# Option_PMIC_RK808.net
KiCad netlist of a schematic drawn in Altium Designer
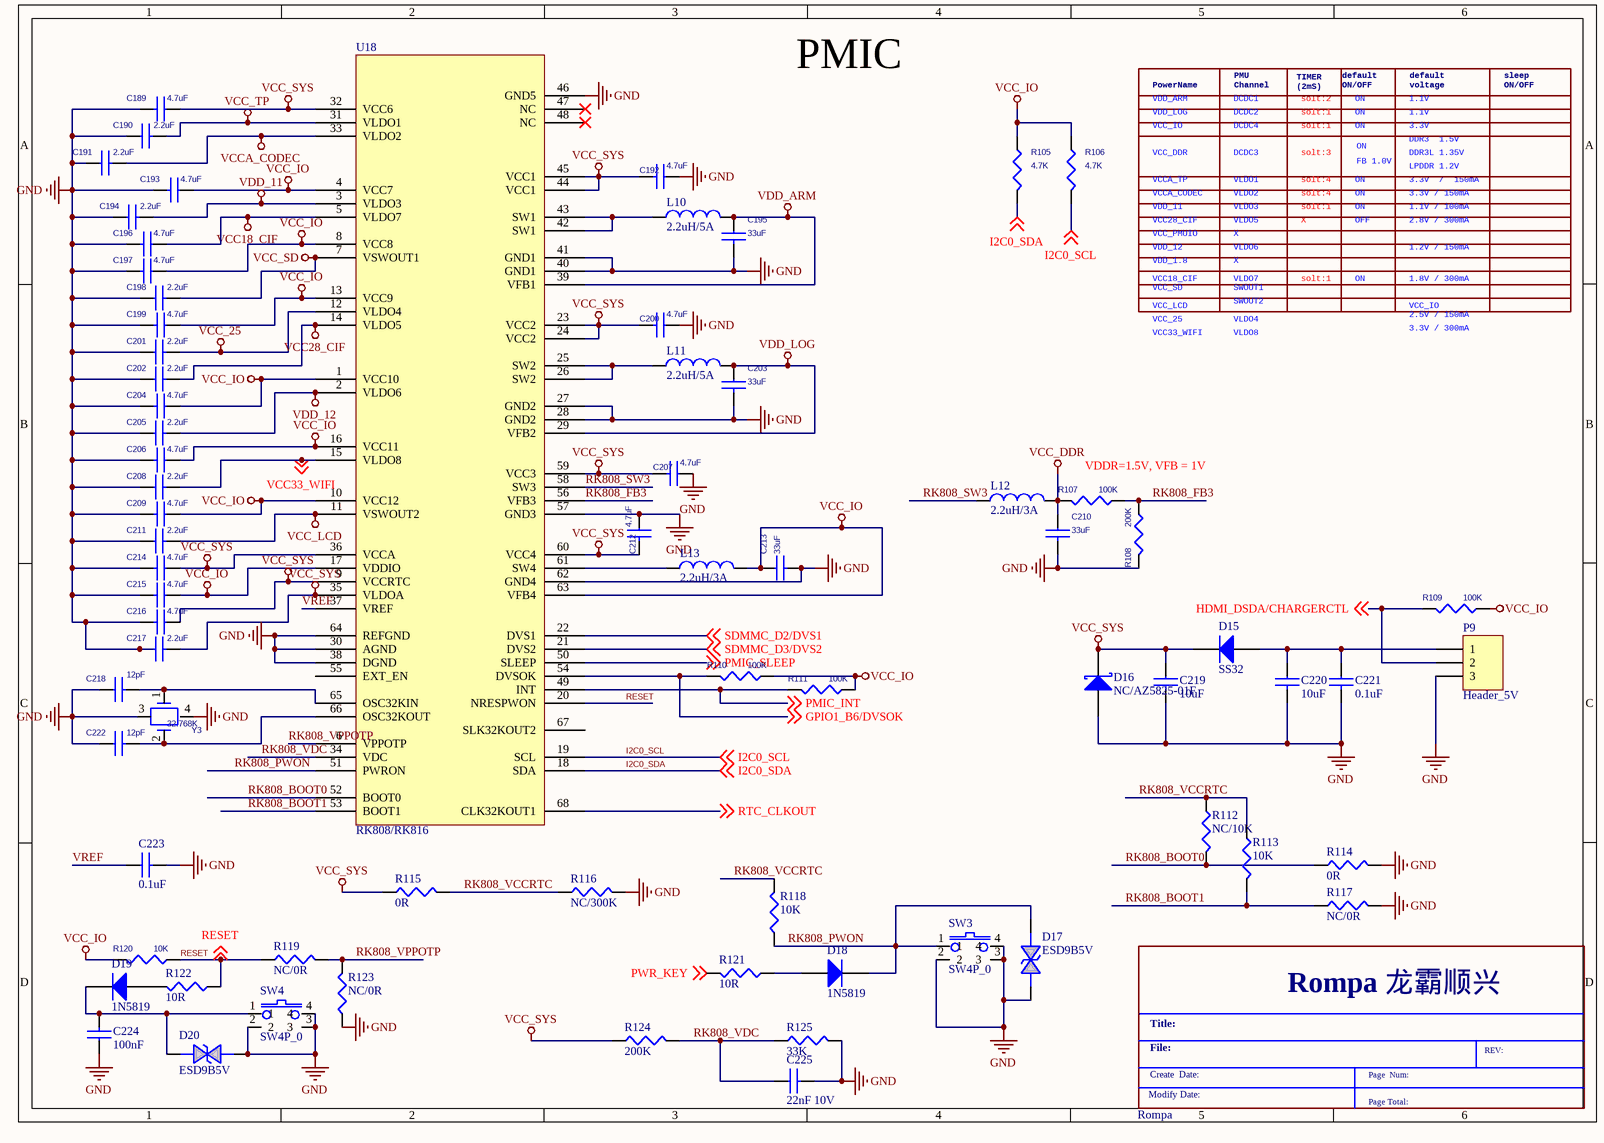
[diagram p0: Option_PMIC_RK808.SchDoc]

(export (version "E")
  (design (tool "Eeschema 10.0.6"))
  (components
    (comp (ref "C189") (value "4.7uF") (footprint "C0603") (libsource (lib "*") (part "CAP NP_4")))
    (comp (ref "C190") (value "2.2uF") (footprint "C0402") (libsource (lib "*") (part "CAP NP_4")))
    (comp (ref "C191") (value "2.2uF") (footprint "C0402") (libsource (lib "*") (part "CAP NP_4")))
    (comp (ref "C192") (value "4.7uF") (footprint "C0603") (libsource (lib "*") (part "CAP NP_4")))
    (comp (ref "C193") (value "4.7uF") (footprint "C0603") (libsource (lib "*") (part "CAP NP_4")))
    (comp (ref "C194") (value "2.2uF") (footprint "C0402") (libsource (lib "*") (part "CAP NP_4")))
    (comp (ref "C195") (value "33uF") (footprint "C0805") (libsource (lib "*") (part "CAP NP_4")))
    (comp (ref "C196") (value "4.7uF") (footprint "C0603") (libsource (lib "*") (part "CAP NP_4")))
    (comp (ref "C197") (value "4.7uF") (footprint "C0603") (libsource (lib "*") (part "CAP NP_4")))
    (comp (ref "C198") (value "2.2uF") (footprint "C0402") (libsource (lib "*") (part "CAP NP_4")))
    (comp (ref "C199") (value "4.7uF") (footprint "C0603") (libsource (lib "*") (part "CAP NP_4")))
    (comp (ref "C200") (value "4.7uF") (footprint "C0603") (libsource (lib "*") (part "CAP NP_4")))
    (comp (ref "C201") (value "2.2uF") (footprint "C0402") (libsource (lib "*") (part "CAP NP_4")))
    (comp (ref "C202") (value "2.2uF") (footprint "C0402") (libsource (lib "*") (part "CAP NP_4")))
    (comp (ref "C203") (value "33uF") (footprint "C0805") (libsource (lib "*") (part "CAP NP_4")))
    (comp (ref "C204") (value "4.7uF") (footprint "C0603") (libsource (lib "*") (part "CAP NP_4")))
    (comp (ref "C205") (value "2.2uF") (footprint "C0402") (libsource (lib "*") (part "CAP NP_4")))
    (comp (ref "C206") (value "4.7uF") (footprint "C0603") (libsource (lib "*") (part "CAP NP_4")))
    (comp (ref "C207") (value "4.7uF") (footprint "C0603") (libsource (lib "*") (part "CAP NP_4")))
    (comp (ref "C208") (value "2.2uF") (footprint "C0402") (libsource (lib "*") (part "CAP NP_4")))
    (comp (ref "C209") (value "4.7uF") (footprint "C0603") (libsource (lib "*") (part "CAP NP_4")))
    (comp (ref "C210") (value "33uF") (footprint "C0805") (libsource (lib "*") (part "CAP NP_4")))
    (comp (ref "C211") (value "2.2uF") (footprint "C0402") (libsource (lib "*") (part "CAP NP_4")))
    (comp (ref "C212") (value "4.7uF") (footprint "C0603") (libsource (lib "*") (part "CAP NP_4")))
    (comp (ref "C213") (value "33uF") (footprint "C0805") (libsource (lib "*") (part "CAP NP_4")))
    (comp (ref "C214") (value "4.7uF") (footprint "C0603") (libsource (lib "*") (part "CAP NP_4")))
    (comp (ref "C215") (value "4.7uF") (footprint "C0603") (libsource (lib "*") (part "CAP NP_4")))
    (comp (ref "C216") (value "4.7uF") (footprint "C0603") (libsource (lib "*") (part "CAP NP_4")))
    (comp (ref "C217") (value "2.2uF") (footprint "C0402") (libsource (lib "*") (part "CAP NP_4")))
    (comp (ref "C218") (value "12pF") (footprint "C0402") (libsource (lib "*") (part "CAP NP_4")))
    (comp (ref "C219")
      (value "10uF")
      (footprint "C0805")
      (description "10V X5R")
      (libsource (lib "RK3128_BETA_V03_20151231_Library") (part "CAP NP_Dup1"))
    )
    (comp (ref "C220")
      (value "10uF")
      (footprint "C0805")
      (description "10V X5R")
      (libsource (lib "RK3128_BETA_V03_20151231_Library") (part "CAP NP_Dup1"))
    )
    (comp (ref "C221")
      (value "0.1uF")
      (footprint "C0402")
      (libsource (lib "RK3128_BETA_V03_20151231_Library") (part "CAP NP"))
    )
    (comp (ref "C222") (value "12pF") (footprint "C0402") (libsource (lib "*") (part "CAP NP_4")))
    (comp (ref "C223")
      (value "0.1uF")
      (footprint "C0402")
      (libsource (lib "RK3128_BETA_V03_20151231_Library") (part "CAP NP"))
    )
    (comp (ref "C224")
      (value "100nF")
      (footprint "C0402")
      (description "16V X7R")
      (libsource (lib "RK3128_BETA_V03_20151231_Library") (part "CAP NP"))
    )
    (comp (ref "C225")
      (value "22nF 10V")
      (footprint "C0402")
      (libsource (lib "RK3128_BETA_V03_20151231_Library") (part "CAP NP"))
    )
    (comp (ref "D15")
      (value "SS32")
      (description "SOD123")
      (fields (field (name "PUBLISHER") "Altium Limited"))
      (libsource (lib "Miscellaneous Devices") (part "Diode"))
    )
    (comp (ref "D16")
      (value "NC/AZ5825-01F")
      (description "AMAZING, FP:DFN1006P2E")
      (fields (field (name "PUBLISHER") "Altium Limited"))
      (libsource (lib "Miscellaneous Devices") (part "Diode BAS70"))
    )
    (comp (ref "D17")
      (value "ESD9B5V")
      (description "FP:E0402N")
      (libsource (lib "RK3128_BETA_V03_20151231_Library") (part "DIODE BI-DIR TRIG"))
    )
    (comp (ref "D18")
      (value "1N5819")
      (fields (field (name "PUBLISHER") "Altium Limited"))
      (libsource (lib "Miscellaneous Devices") (part "Diode"))
    )
    (comp (ref "D19")
      (value "1N5819")
      (fields (field (name "PUBLISHER") "Altium Limited"))
      (libsource (lib "Miscellaneous Devices") (part "Diode"))
    )
    (comp (ref "D20")
      (value "ESD9B5V")
      (description "FP:E0402N")
      (libsource (lib "RK3128_BETA_V03_20151231_Library") (part "DIODE BI-DIR TRIG"))
    )
    (comp (ref "L10") (value "2.2uH/5A") (libsource (lib "Miscellaneous Devices") (part "Inductor")))
    (comp (ref "L11") (value "2.2uH/5A") (libsource (lib "Miscellaneous Devices") (part "Inductor")))
    (comp (ref "L12") (value "2.2uH/3A") (libsource (lib "Miscellaneous Devices") (part "Inductor")))
    (comp (ref "L13") (value "2.2uH/3A") (libsource (lib "Miscellaneous Devices") (part "Inductor")))
    (comp (ref "P9")
      (value "Header_5V")
      (footprint "HDR1X3")
      (description "Header, 3-Pin")
      (fields (field (name "PUBLISHER") "Altium Limited"))
      (libsource (lib "Miscellaneous Connectors") (part "Header 3"))
    )
    (comp (ref "R105")
      (value "4.7K")
      (footprint "R0402")
      (description "ROHS CHIP RES 4.7K 1/16W 5%")
      (libsource (lib "*") (part "RES 1B"))
    )
    (comp (ref "R106")
      (value "4.7K")
      (footprint "R0402")
      (description "ROHS CHIP RES 4.7K 1/16W 5%")
      (libsource (lib "*") (part "RES 1B"))
    )
    (comp (ref "R107")
      (value "100K")
      (footprint "R0402")
      (description "%1")
      (libsource (lib "*") (part "RESISTOR_1"))
    )
    (comp (ref "R108")
      (value "200K")
      (footprint "R0402")
      (description "%1")
      (libsource (lib "") (part "RESISTOR_1_1"))
    )
    (comp (ref "R109")
      (value "100K")
      (footprint "R0402")
      (description "RES,thick film,47KOhm,+/-5%,1/16W,SMD0402")
      (libsource (lib "*") (part "RESISTOR_1"))
    )
    (comp (ref "R110")
      (value "100K")
      (footprint "R0402")
      (description "RES,thick film,47KOhm,+/-5%,1/16W,SMD0402")
      (libsource (lib "*") (part "RESISTOR_1"))
    )
    (comp (ref "R111")
      (value "100K")
      (footprint "R0402")
      (description "RES,thick film,47KOhm,+/-5%,1/16W,SMD0402")
      (libsource (lib "*") (part "RESISTOR_1"))
    )
    (comp (ref "R112")
      (value "NC/10K")
      (footprint "R0402")
      (libsource (lib "RK3128_BETA_V03_20151231_Library") (part "RESISTOR"))
    )
    (comp (ref "R113")
      (value "10K")
      (footprint "R0402")
      (libsource (lib "RK3128_BETA_V03_20151231_Library") (part "RESISTOR"))
    )
    (comp (ref "R114")
      (value "0R")
      (footprint "R0402")
      (libsource (lib "RK3128_BETA_V03_20151231_Library") (part "RESISTOR"))
    )
    (comp (ref "R115")
      (value "0R")
      (footprint "R0402")
      (libsource (lib "RK3128_BETA_V03_20151231_Library") (part "RESISTOR"))
    )
    (comp (ref "R116")
      (value "NC/300K")
      (footprint "R0402")
      (libsource (lib "RK3128_BETA_V03_20151231_Library") (part "RESISTOR"))
    )
    (comp (ref "R117")
      (value "NC/0R")
      (footprint "R0402")
      (libsource (lib "RK3128_BETA_V03_20151231_Library") (part "RESISTOR"))
    )
    (comp (ref "R118")
      (value "10K")
      (footprint "R0402")
      (libsource (lib "RK3128_BETA_V03_20151231_Library") (part "RESISTOR"))
    )
    (comp (ref "R119")
      (value "NC/0R")
      (footprint "R0402")
      (libsource (lib "RK3128_BETA_V03_20151231_Library") (part "RESISTOR"))
    )
    (comp (ref "R120")
      (value "10K")
      (footprint "R0402")
      (description "RES,thick film,47KOhm,+/-5%,1/16W,SMD0402")
      (libsource (lib "*") (part "RESISTOR_1"))
    )
    (comp (ref "R121")
      (value "10R")
      (footprint "R0402")
      (libsource (lib "RK3128_BETA_V03_20151231_Library") (part "RESISTOR"))
    )
    (comp (ref "R122")
      (value "10R")
      (footprint "R0402")
      (libsource (lib "RK3128_BETA_V03_20151231_Library") (part "RESISTOR"))
    )
    (comp (ref "R123")
      (value "NC/0R")
      (footprint "R0402")
      (libsource (lib "RK3128_BETA_V03_20151231_Library") (part "RESISTOR"))
    )
    (comp (ref "R124")
      (value "200K")
      (footprint "R0402")
      (libsource (lib "RK3128_BETA_V03_20151231_Library") (part "RESISTOR"))
    )
    (comp (ref "R125")
      (value "33K")
      (footprint "R0402")
      (libsource (lib "RK3128_BETA_V03_20151231_Library") (part "RESISTOR"))
    )
    (comp (ref "SW3") (value "SW4P_0") (libsource (lib "RK3128_BETA_V03_20151231_Library") (part "SW4P_0")))
    (comp (ref "SW4") (value "SW4P_0") (libsource (lib "RK3128_BETA_V03_20151231_Library") (part "SW4P_0")))
    (comp (ref "U18") (value "RK808/RK816") (libsource (lib "iguide_custom") (part "RK808")))
    (comp (ref "Y3")
      (value "32.768K")
      (footprint "CRY_MC146")
      (description "Crystal,32.768KHz,+/-30ppm,12pF,MC146,-10°C ~ +60   °C")
      (libsource (lib "*") (part "CRYSTAL_0"))
    )
  )
  (nets
    (net (code "1") (name "/RK808_BOOT0") (class "Default")
      (node (ref "R112") (pin "2") (pinfunction "2_2") (pintype "passive"))
      (node (ref "R114") (pin "1") (pinfunction "1_1") (pintype "passive"))
      (node (ref "U18") (pin "52") (pinfunction "BOOT0_52") (pintype "passive"))
    )
    (net (code "2") (name "/RK808_BOOT1") (class "Default")
      (node (ref "R113") (pin "2") (pinfunction "2_2") (pintype "passive"))
      (node (ref "R117") (pin "1") (pinfunction "1_1") (pintype "passive"))
      (node (ref "U18") (pin "53") (pinfunction "BOOT1_53") (pintype "passive"))
    )
    (net (code "3") (name "/RK808_FB3") (class "Default")
      (node (ref "R107") (pin "2") (pinfunction "2_2") (pintype "passive"))
      (node (ref "R108") (pin "2") (pinfunction "2_2") (pintype "passive"))
      (node (ref "U18") (pin "56") (pinfunction "VFB3_56") (pintype "passive"))
    )
    (net (code "4") (name "/RK808_PWON") (class "Default")
      (node (ref "D17") (pin "1") (pinfunction "1_1") (pintype "passive"))
      (node (ref "D18") (pin "2") (pinfunction "K_2") (pintype "passive"))
      (node (ref "R118") (pin "1") (pinfunction "1_1") (pintype "passive"))
      (node (ref "SW3") (pin "1") (pinfunction "1_1") (pintype "passive"))
      (node (ref "U18") (pin "51") (pinfunction "PWRON_51") (pintype "passive"))
    )
    (net (code "5") (name "/RK808_SW3") (class "Default")
      (node (ref "L12") (pin "1") (pinfunction "1_1") (pintype "passive"))
      (node (ref "U18") (pin "58") (pinfunction "SW3_58") (pintype "passive"))
    )
    (net (code "6") (name "/RK808_VCCRTC") (class "Default")
      (node (ref "R112") (pin "1") (pinfunction "1_1") (pintype "passive"))
      (node (ref "R113") (pin "1") (pinfunction "1_1") (pintype "passive"))
      (node (ref "R115") (pin "2") (pinfunction "2_2") (pintype "passive"))
      (node (ref "R116") (pin "1") (pinfunction "1_1") (pintype "passive"))
      (node (ref "R118") (pin "2") (pinfunction "2_2") (pintype "passive"))
    )
    (net (code "7") (name "/RK808_VDC") (class "Default")
      (node (ref "C225") (pin "1") (pinfunction "1_1") (pintype "passive"))
      (node (ref "R124") (pin "2") (pinfunction "2_2") (pintype "passive"))
      (node (ref "R125") (pin "1") (pinfunction "1_1") (pintype "passive"))
      (node (ref "U18") (pin "34") (pinfunction "VDC_34") (pintype "passive"))
    )
    (net (code "8") (name "/RK808_VPPOTP") (class "Default")
      (node (ref "R119") (pin "2") (pinfunction "2_2") (pintype "passive"))
      (node (ref "R123") (pin "2") (pinfunction "2_2") (pintype "passive"))
      (node (ref "U18") (pin "6") (pinfunction "VPPOTP_6") (pintype "passive"))
    )
    (net (code "9") (name "/VREF") (class "Default")
      (node (ref "C223") (pin "1") (pinfunction "1_1") (pintype "passive"))
      (node (ref "U18") (pin "37") (pinfunction "VREF_37") (pintype "passive"))
    )
    (net (code "10") (name "GND") (class "Default")
      (node (ref "C189") (pin "2") (pinfunction "2_2") (pintype "passive"))
      (node (ref "C190") (pin "1") (pinfunction "1_1") (pintype "passive"))
      (node (ref "C191") (pin "1") (pinfunction "1_1") (pintype "passive"))
      (node (ref "C192") (pin "1") (pinfunction "1_1") (pintype "passive"))
      (node (ref "C193") (pin "2") (pinfunction "2_2") (pintype "passive"))
      (node (ref "C194") (pin "1") (pinfunction "1_1") (pintype "passive"))
      (node (ref "C195") (pin "2") (pinfunction "2_2") (pintype "passive"))
      (node (ref "C196") (pin "2") (pinfunction "2_2") (pintype "passive"))
      (node (ref "C197") (pin "2") (pinfunction "2_2") (pintype "passive"))
      (node (ref "C198") (pin "1") (pinfunction "1_1") (pintype "passive"))
      (node (ref "C199") (pin "2") (pinfunction "2_2") (pintype "passive"))
      (node (ref "C200") (pin "1") (pinfunction "1_1") (pintype "passive"))
      (node (ref "C201") (pin "1") (pinfunction "1_1") (pintype "passive"))
      (node (ref "C202") (pin "1") (pinfunction "1_1") (pintype "passive"))
      (node (ref "C203") (pin "2") (pinfunction "2_2") (pintype "passive"))
      (node (ref "C204") (pin "2") (pinfunction "2_2") (pintype "passive"))
      (node (ref "C205") (pin "1") (pinfunction "1_1") (pintype "passive"))
      (node (ref "C206") (pin "2") (pinfunction "2_2") (pintype "passive"))
      (node (ref "C207") (pin "1") (pinfunction "1_1") (pintype "passive"))
      (node (ref "C208") (pin "1") (pinfunction "1_1") (pintype "passive"))
      (node (ref "C209") (pin "2") (pinfunction "2_2") (pintype "passive"))
      (node (ref "C210") (pin "2") (pinfunction "2_2") (pintype "passive"))
      (node (ref "C211") (pin "1") (pinfunction "1_1") (pintype "passive"))
      (node (ref "C212") (pin "1") (pinfunction "1_1") (pintype "passive"))
      (node (ref "C213") (pin "2") (pinfunction "2_2") (pintype "passive"))
      (node (ref "C214") (pin "2") (pinfunction "2_2") (pintype "passive"))
      (node (ref "C215") (pin "2") (pinfunction "2_2") (pintype "passive"))
      (node (ref "C216") (pin "2") (pinfunction "2_2") (pintype "passive"))
      (node (ref "C217") (pin "1") (pinfunction "1_1") (pintype "passive"))
      (node (ref "C218") (pin "1") (pinfunction "1_1") (pintype "passive"))
      (node (ref "C219") (pin "2") (pinfunction "2_2") (pintype "passive"))
      (node (ref "C220") (pin "2") (pinfunction "2_2") (pintype "passive"))
      (node (ref "C221") (pin "2") (pinfunction "2_2") (pintype "passive"))
      (node (ref "C222") (pin "1") (pinfunction "1_1") (pintype "passive"))
      (node (ref "C223") (pin "2") (pinfunction "2_2") (pintype "passive"))
      (node (ref "C224") (pin "1") (pinfunction "1_1") (pintype "passive"))
      (node (ref "C225") (pin "2") (pinfunction "2_2") (pintype "passive"))
      (node (ref "D16") (pin "1") (pinfunction "A_1") (pintype "passive"))
      (node (ref "D17") (pin "2") (pinfunction "2_2") (pintype "passive"))
      (node (ref "D20") (pin "2") (pinfunction "2_2") (pintype "passive"))
      (node (ref "P9") (pin "3") (pinfunction "3_3") (pintype "passive"))
      (node (ref "R108") (pin "1") (pinfunction "1_1") (pintype "passive"))
      (node (ref "R114") (pin "2") (pinfunction "2_2") (pintype "passive"))
      (node (ref "R116") (pin "2") (pinfunction "2_2") (pintype "passive"))
      (node (ref "R117") (pin "2") (pinfunction "2_2") (pintype "passive"))
      (node (ref "R123") (pin "1") (pinfunction "1_1") (pintype "passive"))
      (node (ref "R125") (pin "2") (pinfunction "2_2") (pintype "passive"))
      (node (ref "SW3") (pin "2") (pinfunction "2_2") (pintype "passive"))
      (node (ref "SW3") (pin "3") (pinfunction "3_3") (pintype "passive"))
      (node (ref "SW3") (pin "4") (pinfunction "4_4") (pintype "passive"))
      (node (ref "SW4") (pin "2") (pinfunction "2_2") (pintype "passive"))
      (node (ref "SW4") (pin "3") (pinfunction "3_3") (pintype "passive"))
      (node (ref "SW4") (pin "4") (pinfunction "4_4") (pintype "passive"))
      (node (ref "U18") (pin "27") (pinfunction "GND2_27") (pintype "passive"))
      (node (ref "U18") (pin "28") (pinfunction "GND2_28") (pintype "passive"))
      (node (ref "U18") (pin "30") (pinfunction "AGND_30") (pintype "passive"))
      (node (ref "U18") (pin "38") (pinfunction "DGND_38") (pintype "passive"))
      (node (ref "U18") (pin "40") (pinfunction "GND1_40") (pintype "passive"))
      (node (ref "U18") (pin "41") (pinfunction "GND1_41") (pintype "passive"))
      (node (ref "U18") (pin "46") (pinfunction "GND5_46") (pintype "passive"))
      (node (ref "U18") (pin "57") (pinfunction "GND3_57") (pintype "passive"))
      (node (ref "U18") (pin "62") (pinfunction "GND4_62") (pintype "passive"))
      (node (ref "U18") (pin "64") (pinfunction "REFGND_64") (pintype "passive"))
      (node (ref "Y3") (pin "3") (pinfunction "3_3") (pintype "passive"))
      (node (ref "Y3") (pin "4") (pinfunction "4_4") (pintype "passive"))
    )
    (net (code "11") (name "GPIO1_B6{slash}DVSOK") (class "Default")
      (node (ref "R110") (pin "1") (pinfunction "1_1") (pintype "passive"))
      (node (ref "U18") (pin "54") (pinfunction "DVSOK_54") (pintype "passive"))
    )
    (net (code "12") (name "HDMI_DSDA{slash}CHARGERCTL") (class "Default")
      (node (ref "P9") (pin "2") (pinfunction "2_2") (pintype "passive"))
      (node (ref "R109") (pin "1") (pinfunction "1_1") (pintype "passive"))
    )
    (net (code "13") (name "I2C0_SCL") (class "Default")
      (node (ref "R106") (pin "2") (pinfunction "2_2") (pintype "passive"))
      (node (ref "U18") (pin "19") (pinfunction "SCL_19") (pintype "passive"))
    )
    (net (code "14") (name "I2C0_SDA") (class "Default")
      (node (ref "R105") (pin "2") (pinfunction "2_2") (pintype "passive"))
      (node (ref "U18") (pin "18") (pinfunction "SDA_18") (pintype "passive"))
    )
    (net (code "15") (name "Net-(D15-A)") (class "Default")
      (node (ref "C220") (pin "1") (pinfunction "1_1") (pintype "passive"))
      (node (ref "C221") (pin "1") (pinfunction "1_1") (pintype "passive"))
      (node (ref "D15") (pin "1") (pinfunction "A_1") (pintype "passive"))
      (node (ref "P9") (pin "1") (pinfunction "1_1") (pintype "passive"))
    )
    (net (code "16") (name "Net-(D18-A)") (class "Default")
      (node (ref "D18") (pin "1") (pinfunction "A_1") (pintype "passive"))
      (node (ref "R121") (pin "1") (pinfunction "1_1") (pintype "passive"))
    )
    (net (code "17") (name "Net-(D19-A)") (class "Default")
      (node (ref "D19") (pin "1") (pinfunction "A_1") (pintype "passive"))
      (node (ref "R122") (pin "2") (pinfunction "2_2") (pintype "passive"))
    )
    (net (code "18") (name "Net-(D19-K)") (class "Default")
      (node (ref "C224") (pin "2") (pinfunction "2_2") (pintype "passive"))
      (node (ref "D19") (pin "2") (pinfunction "K_2") (pintype "passive"))
      (node (ref "D20") (pin "1") (pinfunction "1_1") (pintype "passive"))
      (node (ref "SW4") (pin "1") (pinfunction "1_1") (pintype "passive"))
    )
    (net (code "19") (name "Net-(L10-Pad1)") (class "Default")
      (node (ref "L10") (pin "1") (pinfunction "1_1") (pintype "passive"))
      (node (ref "U18") (pin "42") (pinfunction "SW1_42") (pintype "passive"))
      (node (ref "U18") (pin "43") (pinfunction "SW1_43") (pintype "passive"))
    )
    (net (code "20") (name "Net-(L11-Pad1)") (class "Default")
      (node (ref "L11") (pin "1") (pinfunction "1_1") (pintype "passive"))
      (node (ref "U18") (pin "25") (pinfunction "SW2_25") (pintype "passive"))
      (node (ref "U18") (pin "26") (pinfunction "SW2_26") (pintype "passive"))
    )
    (net (code "21") (name "Net-(U18-OSC32KIN)") (class "Default")
      (node (ref "C218") (pin "2") (pinfunction "2_2") (pintype "passive"))
      (node (ref "U18") (pin "65") (pinfunction "OSC32KIN_65") (pintype "passive"))
      (node (ref "Y3") (pin "1") (pinfunction "1_1") (pintype "passive"))
    )
    (net (code "22") (name "Net-(U18-OSC32KOUT)") (class "Default")
      (node (ref "C222") (pin "2") (pinfunction "2_2") (pintype "passive"))
      (node (ref "U18") (pin "66") (pinfunction "OSC32KOUT_66") (pintype "passive"))
      (node (ref "Y3") (pin "2") (pinfunction "2_2") (pintype "passive"))
    )
    (net (code "23") (name "Net-(U18-SW4)") (class "Default")
      (node (ref "L13") (pin "1") (pinfunction "1_1") (pintype "passive"))
      (node (ref "U18") (pin "61") (pinfunction "SW4_61") (pintype "passive"))
    )
    (net (code "24") (name "PMIC_INT") (class "Default")
      (node (ref "R111") (pin "1") (pinfunction "1_1") (pintype "passive"))
      (node (ref "U18") (pin "49") (pinfunction "INT_49") (pintype "passive"))
    )
    (net (code "25") (name "PMIC_SLEEP") (class "Default")
      (node (ref "U18") (pin "50") (pinfunction "SLEEP_50") (pintype "passive"))
    )
    (net (code "26") (name "PWR_KEY") (class "Default")
      (node (ref "R121") (pin "2") (pinfunction "2_2") (pintype "passive"))
    )
    (net (code "27") (name "RESET") (class "Default")
      (node (ref "R119") (pin "1") (pinfunction "1_1") (pintype "passive"))
      (node (ref "R120") (pin "2") (pinfunction "2_2") (pintype "passive"))
      (node (ref "R122") (pin "1") (pinfunction "1_1") (pintype "passive"))
      (node (ref "U18") (pin "20") (pinfunction "NRESPWON_20") (pintype "passive"))
    )
    (net (code "28") (name "RTC_CLKOUT") (class "Default")
      (node (ref "U18") (pin "68") (pinfunction "CLK32KOUT1_68") (pintype "passive"))
    )
    (net (code "29") (name "SDMMC_D2{slash}DVS1") (class "Default")
      (node (ref "U18") (pin "22") (pinfunction "DVS1_22") (pintype "passive"))
    )
    (net (code "30") (name "SDMMC_D3{slash}DVS2") (class "Default")
      (node (ref "U18") (pin "21") (pinfunction "DVS2_21") (pintype "passive"))
    )
    (net (code "31") (name "VCC18_CIF") (class "Default")
      (node (ref "C196") (pin "1") (pinfunction "1_1") (pintype "passive"))
      (node (ref "U18") (pin "5") (pinfunction "VLDO7_5") (pintype "passive"))
    )
    (net (code "32") (name "VCC28_CIF") (class "Default")
      (node (ref "C202") (pin "2") (pinfunction "2_2") (pintype "passive"))
      (node (ref "U18") (pin "14") (pinfunction "VLDO5_14") (pintype "passive"))
    )
    (net (code "33") (name "VCC33_WIFI") (class "Default")
      (node (ref "C208") (pin "2") (pinfunction "2_2") (pintype "passive"))
      (node (ref "U18") (pin "15") (pinfunction "VLDO8_15") (pintype "passive"))
    )
    (net (code "34") (name "VCCA_CODEC") (class "Default")
      (node (ref "C191") (pin "2") (pinfunction "2_2") (pintype "passive"))
      (node (ref "U18") (pin "33") (pinfunction "VLDO2_33") (pintype "passive"))
    )
    (net (code "35") (name "VCC_25") (class "Default")
      (node (ref "C201") (pin "2") (pinfunction "2_2") (pintype "passive"))
      (node (ref "U18") (pin "12") (pinfunction "VLDO4_12") (pintype "passive"))
    )
    (net (code "36") (name "VCC_DDR") (class "Default")
      (node (ref "C210") (pin "1") (pinfunction "1_1") (pintype "passive"))
      (node (ref "L12") (pin "2") (pinfunction "2_2") (pintype "passive"))
      (node (ref "R107") (pin "1") (pinfunction "1_1") (pintype "passive"))
    )
    (net (code "37") (name "VCC_IO") (class "Default")
      (node (ref "C193") (pin "1") (pinfunction "1_1") (pintype "passive"))
      (node (ref "C197") (pin "1") (pinfunction "1_1") (pintype "passive"))
      (node (ref "C199") (pin "1") (pinfunction "1_1") (pintype "passive"))
      (node (ref "C204") (pin "1") (pinfunction "1_1") (pintype "passive"))
      (node (ref "C206") (pin "1") (pinfunction "1_1") (pintype "passive"))
      (node (ref "C209") (pin "1") (pinfunction "1_1") (pintype "passive"))
      (node (ref "C213") (pin "1") (pinfunction "1_1") (pintype "passive"))
      (node (ref "C215") (pin "1") (pinfunction "1_1") (pintype "passive"))
      (node (ref "L13") (pin "2") (pinfunction "2_2") (pintype "passive"))
      (node (ref "R105") (pin "1") (pinfunction "1_1") (pintype "passive"))
      (node (ref "R106") (pin "1") (pinfunction "1_1") (pintype "passive"))
      (node (ref "R109") (pin "2") (pinfunction "2_2") (pintype "passive"))
      (node (ref "R110") (pin "2") (pinfunction "2_2") (pintype "passive"))
      (node (ref "R111") (pin "2") (pinfunction "2_2") (pintype "passive"))
      (node (ref "R120") (pin "1") (pinfunction "1_1") (pintype "passive"))
      (node (ref "U18") (pin "1") (pinfunction "VCC10_1") (pintype "passive"))
      (node (ref "U18") (pin "10") (pinfunction "VCC12_10") (pintype "passive"))
      (node (ref "U18") (pin "13") (pinfunction "VCC9_13") (pintype "passive"))
      (node (ref "U18") (pin "16") (pinfunction "VCC11_16") (pintype "passive"))
      (node (ref "U18") (pin "17") (pinfunction "VDDIO_17") (pintype "passive"))
      (node (ref "U18") (pin "4") (pinfunction "VCC7_4") (pintype "passive"))
      (node (ref "U18") (pin "63") (pinfunction "VFB4_63") (pintype "passive"))
      (node (ref "U18") (pin "8") (pinfunction "VCC8_8") (pintype "passive"))
    )
    (net (code "38") (name "VCC_LCD") (class "Default")
      (node (ref "C211") (pin "2") (pinfunction "2_2") (pintype "passive"))
      (node (ref "U18") (pin "11") (pinfunction "VSWOUT2_11") (pintype "passive"))
    )
    (net (code "39") (name "VCC_SD") (class "Default")
      (node (ref "C198") (pin "2") (pinfunction "2_2") (pintype "passive"))
      (node (ref "U18") (pin "7") (pinfunction "VSWOUT1_7") (pintype "passive"))
    )
    (net (code "40") (name "VCC_SYS") (class "Default")
      (node (ref "C189") (pin "1") (pinfunction "1_1") (pintype "passive"))
      (node (ref "C192") (pin "2") (pinfunction "2_2") (pintype "passive"))
      (node (ref "C200") (pin "2") (pinfunction "2_2") (pintype "passive"))
      (node (ref "C207") (pin "2") (pinfunction "2_2") (pintype "passive"))
      (node (ref "C212") (pin "2") (pinfunction "2_2") (pintype "passive"))
      (node (ref "C214") (pin "1") (pinfunction "1_1") (pintype "passive"))
      (node (ref "C216") (pin "1") (pinfunction "1_1") (pintype "passive"))
      (node (ref "C217") (pin "2") (pinfunction "2_2") (pintype "passive"))
      (node (ref "C219") (pin "1") (pinfunction "1_1") (pintype "passive"))
      (node (ref "D15") (pin "2") (pinfunction "K_2") (pintype "passive"))
      (node (ref "D16") (pin "3") (pinfunction "K_3") (pintype "passive"))
      (node (ref "R115") (pin "1") (pinfunction "1_1") (pintype "passive"))
      (node (ref "R124") (pin "1") (pinfunction "1_1") (pintype "passive"))
      (node (ref "U18") (pin "23") (pinfunction "VCC2_23") (pintype "passive"))
      (node (ref "U18") (pin "24") (pinfunction "VCC2_24") (pintype "passive"))
      (node (ref "U18") (pin "32") (pinfunction "VCC6_32") (pintype "passive"))
      (node (ref "U18") (pin "35") (pinfunction "VLDOA_35") (pintype "passive"))
      (node (ref "U18") (pin "36") (pinfunction "VCCA_36") (pintype "passive"))
      (node (ref "U18") (pin "44") (pinfunction "VCC1_44") (pintype "passive"))
      (node (ref "U18") (pin "45") (pinfunction "VCC1_45") (pintype "passive"))
      (node (ref "U18") (pin "59") (pinfunction "VCC3_59") (pintype "passive"))
      (node (ref "U18") (pin "60") (pinfunction "VCC4_60") (pintype "passive"))
      (node (ref "U18") (pin "9") (pinfunction "VCCRTC_9") (pintype "passive"))
    )
    (net (code "41") (name "VCC_TP") (class "Default")
      (node (ref "C190") (pin "2") (pinfunction "2_2") (pintype "passive"))
      (node (ref "U18") (pin "31") (pinfunction "VLDO1_31") (pintype "passive"))
    )
    (net (code "42") (name "VDD_11") (class "Default")
      (node (ref "C194") (pin "2") (pinfunction "2_2") (pintype "passive"))
      (node (ref "U18") (pin "3") (pinfunction "VLDO3_3") (pintype "passive"))
    )
    (net (code "43") (name "VDD_12") (class "Default")
      (node (ref "C205") (pin "2") (pinfunction "2_2") (pintype "passive"))
      (node (ref "U18") (pin "2") (pinfunction "VLDO6_2") (pintype "passive"))
    )
    (net (code "44") (name "VDD_ARM") (class "Default")
      (node (ref "C195") (pin "1") (pinfunction "1_1") (pintype "passive"))
      (node (ref "L10") (pin "2") (pinfunction "2_2") (pintype "passive"))
      (node (ref "U18") (pin "39") (pinfunction "VFB1_39") (pintype "passive"))
    )
    (net (code "45") (name "VDD_LOG") (class "Default")
      (node (ref "C203") (pin "1") (pinfunction "1_1") (pintype "passive"))
      (node (ref "L11") (pin "2") (pinfunction "2_2") (pintype "passive"))
      (node (ref "U18") (pin "29") (pinfunction "VFB2_29") (pintype "passive"))
    )
    (net (code "46") (name "unconnected-(U18-EXT_EN-Pad55)") (class "Default")
      (node (ref "U18") (pin "55") (pinfunction "EXT_EN_55") (pintype "passive"))
    )
    (net (code "47") (name "unconnected-(U18-NC-Pad47)") (class "Default")
      (node (ref "U18") (pin "47") (pinfunction "NC_47") (pintype "passive+no_connect"))
    )
    (net (code "48") (name "unconnected-(U18-NC-Pad48)") (class "Default")
      (node (ref "U18") (pin "48") (pinfunction "NC_48") (pintype "passive+no_connect"))
    )
    (net (code "49") (name "unconnected-(U18-SLK32KOUT2-Pad67)") (class "Default")
      (node (ref "U18") (pin "67") (pinfunction "SLK32KOUT2_67") (pintype "passive"))
    )
  )
)
